# driveher.net
KiCad netlist of a schematic drawn in EAGLE
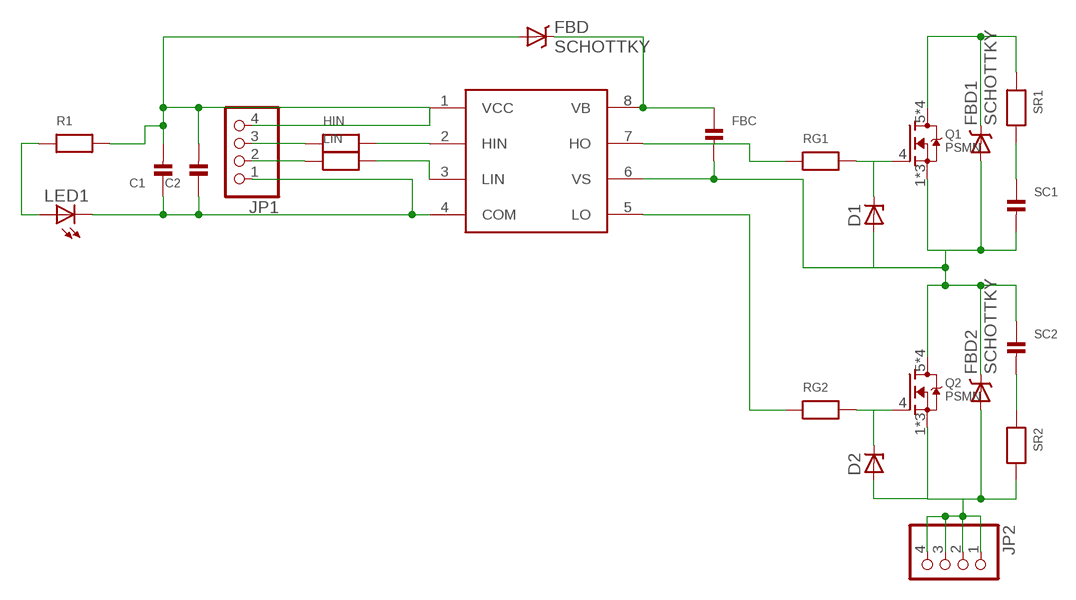
[diagram p0: schematic, sheet 1]

(export (version "E")
  (design (tool "Eeschema 10.0.6"))
  (components
    (comp (ref "C1")
      (value "CAP_CERAMIC1206")
      (footprint "eagle-import:1206")
      (libsource (lib "eagle-import") (part "CAP_CERAMIC1206"))
    )
    (comp (ref "C2")
      (value "CAP_CERAMIC1206")
      (footprint "eagle-import:1206")
      (libsource (lib "eagle-import") (part "CAP_CERAMIC1206"))
    )
    (comp (ref "D1")
      (value "ZENER-DIODESOT23")
      (footprint "eagle-import:SOT23")
      (libsource (lib "eagle-import") (part "ZENER-DIODESOT23"))
    )
    (comp (ref "D2")
      (value "ZENER-DIODESOT23")
      (footprint "eagle-import:SOT23")
      (libsource (lib "eagle-import") (part "ZENER-DIODESOT23"))
    )
    (comp (ref "FBC")
      (value "CAP_CERAMIC1206")
      (footprint "eagle-import:1206")
      (libsource (lib "eagle-import") (part "CAP_CERAMIC1206"))
    )
    (comp (ref "FBD")
      (value "SCHOTTKY")
      (footprint "eagle-import:SMA-DIODE")
      (libsource (lib "eagle-import") (part "SCHOTTKY"))
    )
    (comp (ref "FBD1")
      (value "SCHOTTKY")
      (footprint "eagle-import:SMA-DIODE")
      (libsource (lib "eagle-import") (part "SCHOTTKY"))
    )
    (comp (ref "FBD2")
      (value "SCHOTTKY")
      (footprint "eagle-import:SMA-DIODE")
      (libsource (lib "eagle-import") (part "SCHOTTKY"))
    )
    (comp (ref "HIN")
      (value "RESISTOR0603")
      (footprint "eagle-import:0603")
      (libsource (lib "eagle-import") (part "RESISTOR0603"))
    )
    (comp (ref "JP1")
      (value "HEADER-1X4ROUND")
      (footprint "eagle-import:1X04_ROUND")
      (libsource (lib "eagle-import") (part "HEADER-1X4ROUND"))
    )
    (comp (ref "JP2")
      (value "HEADER-1X4ROUND")
      (footprint "eagle-import:1X04_ROUND")
      (libsource (lib "eagle-import") (part "HEADER-1X4ROUND"))
    )
    (comp (ref "LED1")
      (value "LEDCHIPLED_0603")
      (footprint "eagle-import:CHIPLED_0603")
      (libsource (lib "eagle-import") (part "LEDCHIPLED_0603"))
    )
    (comp (ref "LIN")
      (value "RESISTOR0603")
      (footprint "eagle-import:0603")
      (libsource (lib "eagle-import") (part "RESISTOR0603"))
    )
    (comp (ref "Q1")
      (value "PSMN")
      (footprint "eagle-import:SO-08")
      (libsource (lib "eagle-import") (part "PSMN"))
    )
    (comp (ref "Q2")
      (value "PSMN")
      (footprint "eagle-import:SO-08")
      (libsource (lib "eagle-import") (part "PSMN"))
    )
    (comp (ref "R1")
      (value "RESISTOR0603")
      (footprint "eagle-import:0603")
      (libsource (lib "eagle-import") (part "RESISTOR0603"))
    )
    (comp (ref "RG1")
      (value "RESISTOR0603")
      (footprint "eagle-import:0603")
      (libsource (lib "eagle-import") (part "RESISTOR0603"))
    )
    (comp (ref "RG2")
      (value "RESISTOR0603")
      (footprint "eagle-import:0603")
      (libsource (lib "eagle-import") (part "RESISTOR0603"))
    )
    (comp (ref "SC1")
      (value "CAP_CERAMIC0603")
      (footprint "eagle-import:0603")
      (libsource (lib "eagle-import") (part "CAP_CERAMIC0603"))
    )
    (comp (ref "SC2")
      (value "CAP_CERAMIC0603")
      (footprint "eagle-import:0603")
      (libsource (lib "eagle-import") (part "CAP_CERAMIC0603"))
    )
    (comp (ref "SR1")
      (value "RESISTOR0603")
      (footprint "eagle-import:0603")
      (libsource (lib "eagle-import") (part "RESISTOR0603"))
    )
    (comp (ref "SR2")
      (value "RESISTOR0603")
      (footprint "eagle-import:0603")
      (libsource (lib "eagle-import") (part "RESISTOR0603"))
    )
    (comp (ref "U$1")
      (value "IRS218-67")
      (footprint "eagle-import:SO-08")
      (libsource (lib "eagle-import") (part "IRS218-67"))
    )
  )
  (nets
    (net (code "1") (name "/GND") (class "Default")
      (node (ref "C1") (pin "1") (pinfunction "P$1_1") (pintype "passive"))
      (node (ref "C2") (pin "1") (pinfunction "P$1_1") (pintype "passive"))
      (node (ref "D2") (pin "1") (pinfunction "A_1") (pintype "passive"))
      (node (ref "FBD2") (pin "A") (pinfunction "A_A") (pintype "passive"))
      (node (ref "JP1") (pin "1") (pinfunction "1_1") (pintype "passive"))
      (node (ref "JP2") (pin "1") (pinfunction "1_1") (pintype "passive"))
      (node (ref "JP2") (pin "2") (pinfunction "2_2") (pintype "passive"))
      (node (ref "JP2") (pin "3") (pinfunction "3_3") (pintype "passive"))
      (node (ref "JP2") (pin "4") (pinfunction "4_4") (pintype "passive"))
      (node (ref "LED1") (pin "C") (pinfunction "C_C") (pintype "passive"))
      (node (ref "Q2") (pin "1") (pinfunction "S_1") (pintype "bidirectional"))
      (node (ref "Q2") (pin "2") (pinfunction "S_2") (pintype "bidirectional"))
      (node (ref "Q2") (pin "3") (pinfunction "S_3") (pintype "bidirectional"))
      (node (ref "SR2") (pin "2") (pinfunction "2_2") (pintype "passive"))
      (node (ref "U$1") (pin "4") (pinfunction "COM_4") (pintype "bidirectional"))
    )
    (net (code "2") (name "Net-(C1-P$2)") (class "Default")
      (node (ref "C1") (pin "2") (pinfunction "P$2_2") (pintype "passive"))
      (node (ref "C2") (pin "2") (pinfunction "P$2_2") (pintype "passive"))
      (node (ref "FBD") (pin "A") (pinfunction "A_A") (pintype "passive"))
      (node (ref "JP1") (pin "4") (pinfunction "4_4") (pintype "passive"))
      (node (ref "R1") (pin "2") (pinfunction "2_2") (pintype "passive"))
      (node (ref "U$1") (pin "1") (pinfunction "VCC_1") (pintype "bidirectional"))
    )
    (net (code "3") (name "Net-(D1-A)") (class "Default")
      (node (ref "D1") (pin "1") (pinfunction "A_1") (pintype "passive"))
      (node (ref "FBC") (pin "2") (pinfunction "P$2_2") (pintype "passive"))
      (node (ref "FBD1") (pin "A") (pinfunction "A_A") (pintype "passive"))
      (node (ref "FBD2") (pin "C") (pinfunction "C_C") (pintype "passive"))
      (node (ref "Q1") (pin "1") (pinfunction "S_1") (pintype "bidirectional"))
      (node (ref "Q1") (pin "2") (pinfunction "S_2") (pintype "bidirectional"))
      (node (ref "Q1") (pin "3") (pinfunction "S_3") (pintype "bidirectional"))
      (node (ref "Q2") (pin "5") (pinfunction "D_5") (pintype "bidirectional"))
      (node (ref "Q2") (pin "6") (pinfunction "D_6") (pintype "bidirectional"))
      (node (ref "Q2") (pin "7") (pinfunction "D_7") (pintype "bidirectional"))
      (node (ref "Q2") (pin "8") (pinfunction "D_8") (pintype "bidirectional"))
      (node (ref "SC1") (pin "2") (pinfunction "P$2_2") (pintype "passive"))
      (node (ref "SC2") (pin "1") (pinfunction "P$1_1") (pintype "passive"))
      (node (ref "U$1") (pin "6") (pinfunction "VS_6") (pintype "bidirectional"))
    )
    (net (code "4") (name "Net-(D1-C)") (class "Default")
      (node (ref "D1") (pin "3") (pinfunction "C_3") (pintype "passive"))
      (node (ref "Q1") (pin "4") (pinfunction "G_4") (pintype "bidirectional"))
      (node (ref "RG1") (pin "2") (pinfunction "2_2") (pintype "passive"))
    )
    (net (code "5") (name "Net-(D2-C)") (class "Default")
      (node (ref "D2") (pin "3") (pinfunction "C_3") (pintype "passive"))
      (node (ref "Q2") (pin "4") (pinfunction "G_4") (pintype "bidirectional"))
      (node (ref "RG2") (pin "2") (pinfunction "2_2") (pintype "passive"))
    )
    (net (code "6") (name "Net-(FBC-P$1)") (class "Default")
      (node (ref "FBC") (pin "1") (pinfunction "P$1_1") (pintype "passive"))
      (node (ref "FBD") (pin "C") (pinfunction "C_C") (pintype "passive"))
      (node (ref "U$1") (pin "8") (pinfunction "VB_8") (pintype "bidirectional"))
    )
    (net (code "7") (name "Net-(FBD1-PadC)") (class "Default")
      (node (ref "FBD1") (pin "C") (pinfunction "C_C") (pintype "passive"))
      (node (ref "Q1") (pin "5") (pinfunction "D_5") (pintype "bidirectional"))
      (node (ref "Q1") (pin "6") (pinfunction "D_6") (pintype "bidirectional"))
      (node (ref "Q1") (pin "7") (pinfunction "D_7") (pintype "bidirectional"))
      (node (ref "Q1") (pin "8") (pinfunction "D_8") (pintype "bidirectional"))
      (node (ref "SR1") (pin "1") (pinfunction "1_1") (pintype "passive"))
    )
    (net (code "8") (name "Net-(HIN-Pad1)") (class "Default")
      (node (ref "HIN") (pin "1") (pinfunction "1_1") (pintype "passive"))
      (node (ref "JP1") (pin "3") (pinfunction "3_3") (pintype "passive"))
    )
    (net (code "9") (name "Net-(JP1-Pad2)") (class "Default")
      (node (ref "JP1") (pin "2") (pinfunction "2_2") (pintype "passive"))
      (node (ref "LIN") (pin "1") (pinfunction "1_1") (pintype "passive"))
    )
    (net (code "10") (name "Net-(LED1-PadA)") (class "Default")
      (node (ref "LED1") (pin "A") (pinfunction "A_A") (pintype "passive"))
      (node (ref "R1") (pin "1") (pinfunction "1_1") (pintype "passive"))
    )
    (net (code "11") (name "Net-(SC1-P$1)") (class "Default")
      (node (ref "SC1") (pin "1") (pinfunction "P$1_1") (pintype "passive"))
      (node (ref "SR1") (pin "2") (pinfunction "2_2") (pintype "passive"))
    )
    (net (code "12") (name "Net-(SC2-P$2)") (class "Default")
      (node (ref "SC2") (pin "2") (pinfunction "P$2_2") (pintype "passive"))
      (node (ref "SR2") (pin "1") (pinfunction "1_1") (pintype "passive"))
    )
    (net (code "13") (name "Net-(U$1-HIN)") (class "Default")
      (node (ref "HIN") (pin "2") (pinfunction "2_2") (pintype "passive"))
      (node (ref "U$1") (pin "2") (pinfunction "HIN_2") (pintype "bidirectional"))
    )
    (net (code "14") (name "Net-(U$1-HO)") (class "Default")
      (node (ref "RG1") (pin "1") (pinfunction "1_1") (pintype "passive"))
      (node (ref "U$1") (pin "7") (pinfunction "HO_7") (pintype "bidirectional"))
    )
    (net (code "15") (name "Net-(U$1-LIN)") (class "Default")
      (node (ref "LIN") (pin "2") (pinfunction "2_2") (pintype "passive"))
      (node (ref "U$1") (pin "3") (pinfunction "LIN_3") (pintype "bidirectional"))
    )
    (net (code "16") (name "Net-(U$1-LO)") (class "Default")
      (node (ref "RG2") (pin "1") (pinfunction "1_1") (pintype "passive"))
      (node (ref "U$1") (pin "5") (pinfunction "LO_5") (pintype "bidirectional"))
    )
  )
)
